# led_atmega_usb_connected.net
KiCad netlist of a schematic drawn in EAGLE
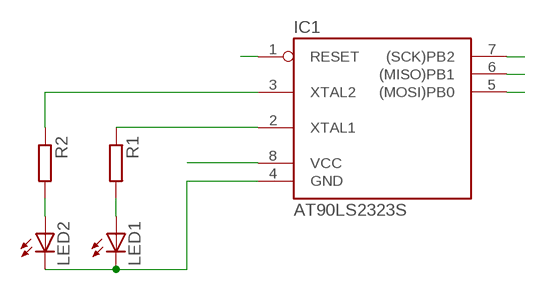
[diagram p0: schematic, sheet 1]

(export (version "E")
  (design (tool "Eeschema 10.0.6"))
  (components
    (comp (ref "IC1")
      (value "AT90LS2323S")
      (footprint "eagle-import:SOIC8")
      (libsource (lib "eagle-import") (part "AT902323SLS"))
    )
    (comp (ref "LED1")
      (value "LEDSMT1206")
      (footprint "eagle-import:1206")
      (libsource (lib "eagle-import") (part "LEDSMT1206"))
    )
    (comp (ref "LED2")
      (value "LEDSMT1206")
      (footprint "eagle-import:1206")
      (libsource (lib "eagle-import") (part "LEDSMT1206"))
    )
    (comp (ref "R1")
      (value "R-EU_R1206")
      (footprint "eagle-import:R1206")
      (libsource (lib "eagle-import") (part "R-EU_R1206"))
    )
    (comp (ref "R2")
      (value "R-EU_R1206")
      (footprint "eagle-import:R1206")
      (libsource (lib "eagle-import") (part "R-EU_R1206"))
    )
  )
  (nets
    (net (code "1") (name "Net-(IC1-GND)") (class "Default")
      (node (ref "IC1") (pin "4") (pinfunction "GND_4") (pintype "power_in"))
      (node (ref "LED1") (pin "C") (pinfunction "C_C") (pintype "passive"))
      (node (ref "LED2") (pin "C") (pinfunction "C_C") (pintype "passive"))
    )
    (net (code "2") (name "Net-(IC1-XTAL1)") (class "Default")
      (node (ref "IC1") (pin "2") (pinfunction "XTAL1_2") (pintype "bidirectional"))
      (node (ref "R1") (pin "1") (pinfunction "1_1") (pintype "passive"))
    )
    (net (code "3") (name "Net-(IC1-XTAL2)") (class "Default")
      (node (ref "IC1") (pin "3") (pinfunction "XTAL2_3") (pintype "bidirectional"))
      (node (ref "R2") (pin "1") (pinfunction "1_1") (pintype "passive"))
    )
    (net (code "4") (name "Net-(LED1-PadA)") (class "Default")
      (node (ref "LED1") (pin "A") (pinfunction "A_A") (pintype "passive"))
      (node (ref "R1") (pin "2") (pinfunction "2_2") (pintype "passive"))
    )
    (net (code "5") (name "Net-(LED2-PadA)") (class "Default")
      (node (ref "LED2") (pin "A") (pinfunction "A_A") (pintype "passive"))
      (node (ref "R2") (pin "2") (pinfunction "2_2") (pintype "passive"))
    )
    (net (code "6") (name "unconnected-(IC1-(MISO)PB1-Pad6)") (class "Default")
      (node (ref "IC1") (pin "6") (pinfunction "(MISO)PB1_6") (pintype "bidirectional"))
    )
    (net (code "7") (name "unconnected-(IC1-(MOSI)PB0-Pad5)") (class "Default")
      (node (ref "IC1") (pin "5") (pinfunction "(MOSI)PB0_5") (pintype "bidirectional"))
    )
    (net (code "8") (name "unconnected-(IC1-(SCK)PB2-Pad7)") (class "Default")
      (node (ref "IC1") (pin "7") (pinfunction "(SCK)PB2_7") (pintype "bidirectional"))
    )
    (net (code "9") (name "unconnected-(IC1-RESET-Pad1)") (class "Default")
      (node (ref "IC1") (pin "1") (pinfunction "RESET_1") (pintype "input"))
    )
    (net (code "10") (name "unconnected-(IC1-VCC-Pad8)") (class "Default")
      (node (ref "IC1") (pin "8") (pinfunction "VCC_8") (pintype "power_in"))
    )
  )
)
